# delonghi-led-v012.net
KiCad netlist of a schematic drawn in EAGLE
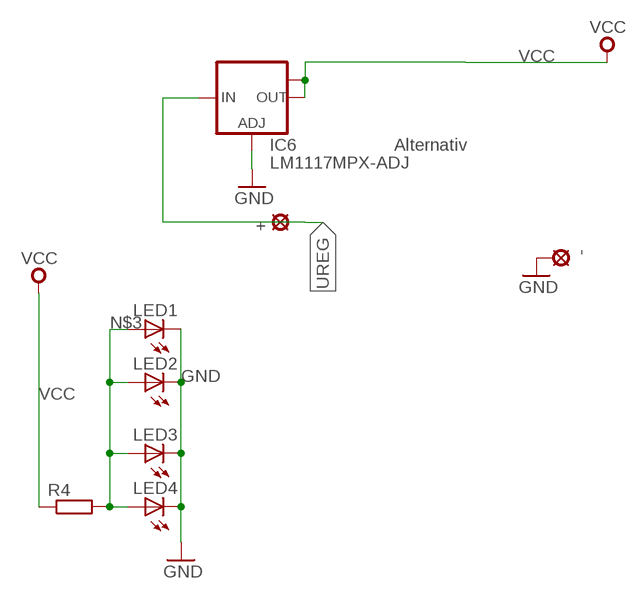
[diagram p0: schematic, sheet 1]

(export (version "E")
  (design (tool "Eeschema 10.0.6"))
  (components
    (comp (ref "+")
      (value "LSP10")
      (footprint "eagle-import:LSP10")
      (libsource (lib "eagle-import") (part "LSP10"))
    )
    (comp (ref "-")
      (value "LSP10")
      (footprint "eagle-import:LSP10")
      (libsource (lib "eagle-import") (part "LSP10"))
    )
    (comp (ref "IC6")
      (value "LM1117MPX-ADJ")
      (footprint "eagle-import:SOT223")
      (libsource (lib "eagle-import") (part "LM1117MPX-ADJ"))
    )
    (comp (ref "LED1")
      (value "LEDCHIPLED_0805")
      (footprint "eagle-import:CHIPLED_0805")
      (libsource (lib "eagle-import") (part "LEDCHIPLED_0805"))
    )
    (comp (ref "LED2")
      (value "LEDCHIPLED_0805")
      (footprint "eagle-import:CHIPLED_0805")
      (libsource (lib "eagle-import") (part "LEDCHIPLED_0805"))
    )
    (comp (ref "LED3")
      (value "LEDCHIPLED_0805")
      (footprint "eagle-import:CHIPLED_0805")
      (libsource (lib "eagle-import") (part "LEDCHIPLED_0805"))
    )
    (comp (ref "LED4")
      (value "LEDCHIPLED_0805")
      (footprint "eagle-import:CHIPLED_0805")
      (libsource (lib "eagle-import") (part "LEDCHIPLED_0805"))
    )
    (comp (ref "R4")
      (value "R-EU_M0805")
      (footprint "eagle-import:M0805")
      (libsource (lib "eagle-import") (part "R-EU_M0805"))
    )
  )
  (nets
    (net (code "1") (name "/N$3") (class "Default")
      (node (ref "LED1") (pin "A") (pinfunction "A_A") (pintype "passive"))
      (node (ref "LED2") (pin "A") (pinfunction "A_A") (pintype "passive"))
      (node (ref "LED3") (pin "A") (pinfunction "A_A") (pintype "passive"))
      (node (ref "LED4") (pin "A") (pinfunction "A_A") (pintype "passive"))
      (node (ref "R4") (pin "2") (pinfunction "2_2") (pintype "passive"))
    )
    (net (code "2") (name "GND") (class "Default")
      (node (ref "-") (pin "MP") (pinfunction "MP_MP") (pintype "passive"))
      (node (ref "IC6") (pin "1") (pinfunction "ADJ_1") (pintype "input"))
      (node (ref "LED1") (pin "C") (pinfunction "C_C") (pintype "passive"))
      (node (ref "LED2") (pin "C") (pinfunction "C_C") (pintype "passive"))
      (node (ref "LED3") (pin "C") (pinfunction "C_C") (pintype "passive"))
      (node (ref "LED4") (pin "C") (pinfunction "C_C") (pintype "passive"))
    )
    (net (code "3") (name "UREG") (class "Default")
      (node (ref "+") (pin "MP") (pinfunction "MP_MP") (pintype "passive"))
      (node (ref "IC6") (pin "3") (pinfunction "IN_3") (pintype "input"))
    )
    (net (code "4") (name "VCC") (class "Default")
      (node (ref "IC6") (pin "2") (pinfunction "OUT_2") (pintype "passive"))
      (node (ref "IC6") (pin "TAB") (pinfunction "OUT1_TAB") (pintype "passive"))
      (node (ref "R4") (pin "1") (pinfunction "1_1") (pintype "passive"))
    )
  )
)
